# debug.net
KiCad netlist of a schematic drawn in Altium Designer
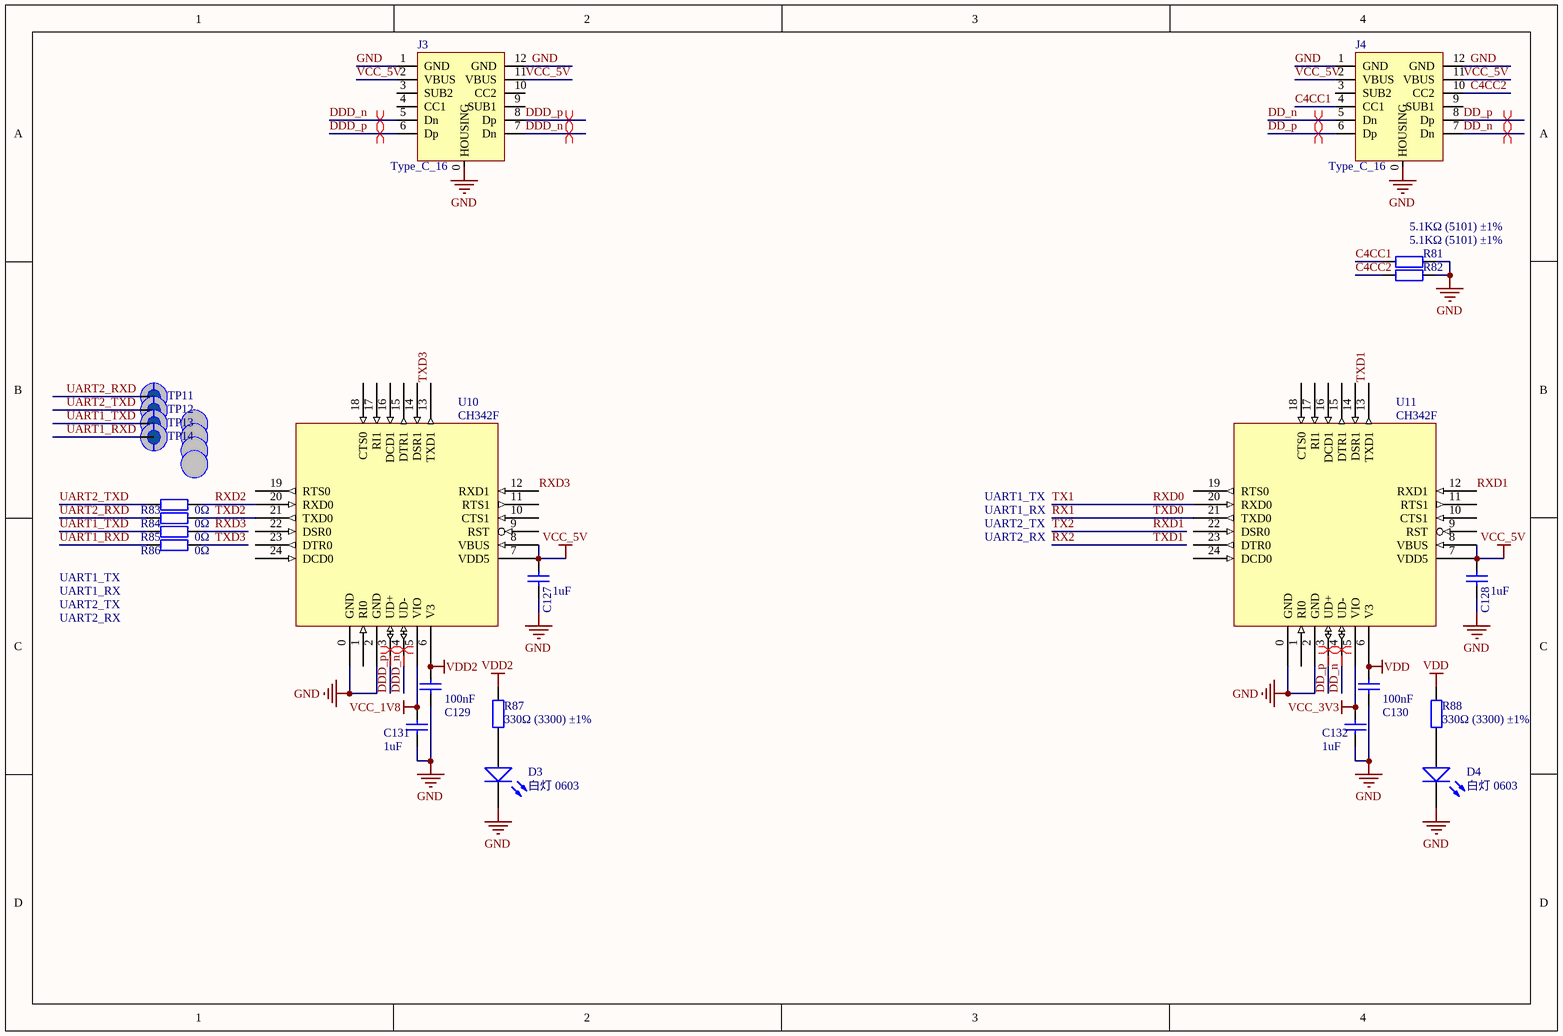
[diagram p0: debug.SchDoc]

(export (version "E")
  (design (tool "Eeschema 10.0.6"))
  (components
    (comp (ref "C127")
      (value "1uF")
      (footprint "0805_C")
      (description "贴片电容")
      (libsource (lib "嘉立创标准库") (part "0603 1uF (105) 10% 50V"))
    )
    (comp (ref "C128")
      (value "1uF")
      (footprint "0805_C")
      (description "贴片电容")
      (libsource (lib "嘉立创标准库") (part "0603 1uF (105) 10% 50V"))
    )
    (comp (ref "C129")
      (value "100nF")
      (footprint "0805_C")
      (description "贴片电容")
      (libsource (lib "嘉立创标准库") (part "0402 100nF (104) 10% 16V"))
    )
    (comp (ref "C130")
      (value "100nF")
      (footprint "0805_C")
      (description "贴片电容")
      (libsource (lib "嘉立创标准库") (part "0402 100nF (104) 10% 16V"))
    )
    (comp (ref "C131")
      (value "1uF")
      (footprint "0805_C")
      (description "贴片电容")
      (libsource (lib "嘉立创标准库") (part "0603 1uF (105) 10% 50V"))
    )
    (comp (ref "C132")
      (value "1uF")
      (footprint "0805_C")
      (description "贴片电容")
      (libsource (lib "嘉立创标准库") (part "0603 1uF (105) 10% 50V"))
    )
    (comp (ref "D3")
      (value "白灯 0603")
      (footprint "0805_LED_S1")
      (description "发光二极管")
      (libsource (lib "嘉立创标准库") (part "0603 白灯"))
    )
    (comp (ref "D4")
      (value "白灯 0603")
      (footprint "0805_LED_S1")
      (description "发光二极管")
      (libsource (lib "嘉立创标准库") (part "0603 白灯"))
    )
    (comp (ref "J3")
      (value "Type_C_16")
      (footprint "USB type C  16pin")
      (description "USB type C 16pin")
      (libsource (lib "yy_tech") (part "Type_C_16"))
    )
    (comp (ref "J4")
      (value "Type_C_16")
      (footprint "USB type C  16pin")
      (description "USB type C 16pin")
      (libsource (lib "yy_tech") (part "Type_C_16"))
    )
    (comp (ref "R81")
      (value "5.1KΩ (5101) ±1%")
      (footprint "0402_R")
      (description "贴片电阻")
      (libsource (lib "嘉立创标准库") (part "0402 5.1KΩ (5101) 1%"))
    )
    (comp (ref "R82")
      (value "5.1KΩ (5101) ±1%")
      (footprint "0402_R")
      (description "贴片电阻")
      (libsource (lib "嘉立创标准库") (part "0402 5.1KΩ (5101) 1%"))
    )
    (comp (ref "R83")
      (value "0Ω")
      (footprint "0805_R")
      (description "贴片电阻")
      (libsource (lib "Miscellaneous Devices LC") (part "0805 0Ω (0R0) 1%"))
    )
    (comp (ref "R84")
      (value "0Ω")
      (footprint "0805_R")
      (description "贴片电阻")
      (libsource (lib "Miscellaneous Devices LC") (part "0805 0Ω (0R0) 1%"))
    )
    (comp (ref "R85")
      (value "0Ω")
      (footprint "0805_R")
      (description "贴片电阻")
      (libsource (lib "Miscellaneous Devices LC") (part "0805 0Ω (0R0) 1%"))
    )
    (comp (ref "R86")
      (value "0Ω")
      (footprint "0805_R")
      (description "贴片电阻")
      (libsource (lib "Miscellaneous Devices LC") (part "0805 0Ω (0R0) 1%"))
    )
    (comp (ref "R87")
      (value "330Ω (3300) ±1%")
      (footprint "0805_R")
      (description "贴片电阻")
      (libsource (lib "Miscellaneous Devices LC") (part "0402 330Ω (3300) 1%"))
    )
    (comp (ref "R88")
      (value "330Ω (3300) ±1%")
      (footprint "0805_R")
      (description "贴片电阻")
      (libsource (lib "Miscellaneous Devices LC") (part "0402 330Ω (3300) 1%"))
    )
    (comp (ref "TP11")
      (value "test-point")
      (footprint "POINT")
      (description "测试点")
      (libsource (lib "五向开关") (part "test-point"))
    )
    (comp (ref "TP12")
      (value "test-point")
      (footprint "POINT")
      (description "测试点")
      (libsource (lib "五向开关") (part "test-point"))
    )
    (comp (ref "TP13")
      (value "test-point")
      (footprint "POINT")
      (description "测试点")
      (libsource (lib "五向开关") (part "test-point"))
    )
    (comp (ref "TP14")
      (value "test-point")
      (footprint "POINT")
      (description "测试点")
      (libsource (lib "五向开关") (part "test-point"))
    )
    (comp (ref "U10")
      (value "CH342F")
      (footprint "QFN24_4X4")
      (description "USB to dual enhanced TTL Serial / 2*UART")
      (libsource (lib "CHXXX") (part "CH342F"))
    )
    (comp (ref "U11")
      (value "CH342F")
      (footprint "QFN24_4X4")
      (description "USB to dual enhanced TTL Serial / 2*UART")
      (libsource (lib "CHXXX") (part "CH342F"))
    )
  )
  (nets
    (net (code "1") (name "/C4CC1") (class "Default")
      (node (ref "J4") (pin "4") (pinfunction "CC1_4") (pintype "passive"))
      (node (ref "R81") (pin "2") (pinfunction "2_2") (pintype "passive"))
    )
    (net (code "2") (name "/C4CC2") (class "Default")
      (node (ref "J4") (pin "10") (pinfunction "CC2_10") (pintype "passive"))
      (node (ref "R82") (pin "2") (pinfunction "2_2") (pintype "passive"))
    )
    (net (code "3") (name "/DDD_n") (class "Default")
      (node (ref "J3") (pin "5") (pinfunction "Dn_5") (pintype "passive"))
      (node (ref "J3") (pin "7") (pinfunction "Dn_7") (pintype "passive"))
      (node (ref "U10") (pin "4") (pinfunction "UD-_4") (pintype "bidirectional"))
    )
    (net (code "4") (name "/DDD_p") (class "Default")
      (node (ref "J3") (pin "6") (pinfunction "Dp_6") (pintype "passive"))
      (node (ref "J3") (pin "8") (pinfunction "Dp_8") (pintype "passive"))
      (node (ref "U10") (pin "3") (pinfunction "UD+_3") (pintype "bidirectional"))
    )
    (net (code "5") (name "/DD_n") (class "Default")
      (node (ref "J4") (pin "5") (pinfunction "Dn_5") (pintype "passive"))
      (node (ref "J4") (pin "7") (pinfunction "Dn_7") (pintype "passive"))
      (node (ref "U11") (pin "4") (pinfunction "UD-_4") (pintype "bidirectional"))
    )
    (net (code "6") (name "/DD_p") (class "Default")
      (node (ref "J4") (pin "6") (pinfunction "Dp_6") (pintype "passive"))
      (node (ref "J4") (pin "8") (pinfunction "Dp_8") (pintype "passive"))
      (node (ref "U11") (pin "3") (pinfunction "UD+_3") (pintype "bidirectional"))
    )
    (net (code "7") (name "/RX1") (class "Default")
      (node (ref "U11") (pin "21") (pinfunction "TXD0_21") (pintype "output"))
    )
    (net (code "8") (name "/RX2") (class "Default")
      (node (ref "U11") (pin "13") (pinfunction "TXD1_13") (pintype "output"))
    )
    (net (code "9") (name "/RXD0") (class "Default")
      (node (ref "U11") (pin "20") (pinfunction "RXD0_20") (pintype "input"))
    )
    (net (code "10") (name "/RXD1") (class "Default")
      (node (ref "U11") (pin "12") (pinfunction "RXD1_12") (pintype "input"))
    )
    (net (code "11") (name "/RXD2") (class "Default")
      (node (ref "R83") (pin "2") (pinfunction "2_2") (pintype "passive"))
      (node (ref "U10") (pin "20") (pinfunction "RXD0_20") (pintype "input"))
    )
    (net (code "12") (name "/RXD3") (class "Default")
      (node (ref "R85") (pin "2") (pinfunction "2_2") (pintype "passive"))
      (node (ref "U10") (pin "12") (pinfunction "RXD1_12") (pintype "input"))
    )
    (net (code "13") (name "/TXD2") (class "Default")
      (node (ref "R84") (pin "2") (pinfunction "2_2") (pintype "passive"))
      (node (ref "U10") (pin "21") (pinfunction "TXD0_21") (pintype "output"))
    )
    (net (code "14") (name "/TXD3") (class "Default")
      (node (ref "R86") (pin "2") (pinfunction "2_2") (pintype "passive"))
      (node (ref "U10") (pin "13") (pinfunction "TXD1_13") (pintype "output"))
    )
    (net (code "15") (name "/UART1_RXD") (class "Default")
      (node (ref "R86") (pin "1") (pinfunction "1_1") (pintype "passive"))
      (node (ref "TP14") (pin "1") (pinfunction "point_1") (pintype "passive"))
    )
    (net (code "16") (name "/UART1_TXD") (class "Default")
      (node (ref "R85") (pin "1") (pinfunction "1_1") (pintype "passive"))
      (node (ref "TP13") (pin "1") (pinfunction "point_1") (pintype "passive"))
    )
    (net (code "17") (name "/UART2_RXD") (class "Default")
      (node (ref "R84") (pin "1") (pinfunction "1_1") (pintype "passive"))
      (node (ref "TP11") (pin "1") (pinfunction "point_1") (pintype "passive"))
    )
    (net (code "18") (name "/UART2_TXD") (class "Default")
      (node (ref "R83") (pin "1") (pinfunction "1_1") (pintype "passive"))
      (node (ref "TP12") (pin "1") (pinfunction "point_1") (pintype "passive"))
    )
    (net (code "19") (name "GND") (class "Default")
      (node (ref "C127") (pin "1") (pinfunction "1_1") (pintype "passive"))
      (node (ref "C128") (pin "1") (pinfunction "1_1") (pintype "passive"))
      (node (ref "C129") (pin "1") (pinfunction "1_1") (pintype "passive"))
      (node (ref "C130") (pin "1") (pinfunction "1_1") (pintype "passive"))
      (node (ref "C131") (pin "1") (pinfunction "1_1") (pintype "passive"))
      (node (ref "C132") (pin "1") (pinfunction "1_1") (pintype "passive"))
      (node (ref "D3") (pin "K") (pinfunction "K_K") (pintype "passive"))
      (node (ref "D4") (pin "K") (pinfunction "K_K") (pintype "passive"))
      (node (ref "J3") (pin "0") (pinfunction "HOUSING_0") (pintype "passive"))
      (node (ref "J3") (pin "1") (pinfunction "GND_1") (pintype "passive"))
      (node (ref "J3") (pin "12") (pinfunction "GND_12") (pintype "passive"))
      (node (ref "J4") (pin "0") (pinfunction "HOUSING_0") (pintype "passive"))
      (node (ref "J4") (pin "1") (pinfunction "GND_1") (pintype "passive"))
      (node (ref "J4") (pin "12") (pinfunction "GND_12") (pintype "passive"))
      (node (ref "R81") (pin "1") (pinfunction "1_1") (pintype "passive"))
      (node (ref "R82") (pin "1") (pinfunction "1_1") (pintype "passive"))
      (node (ref "U10") (pin "0") (pinfunction "GND_0") (pintype "power_in"))
      (node (ref "U10") (pin "2") (pinfunction "GND_2") (pintype "power_in"))
      (node (ref "U11") (pin "0") (pinfunction "GND_0") (pintype "power_in"))
      (node (ref "U11") (pin "2") (pinfunction "GND_2") (pintype "power_in"))
    )
    (net (code "20") (name "Net-(D3-PadA)") (class "Default")
      (node (ref "D3") (pin "A") (pinfunction "A_A") (pintype "passive"))
      (node (ref "R87") (pin "1") (pinfunction "1_1") (pintype "passive"))
    )
    (net (code "21") (name "Net-(D4-PadA)") (class "Default")
      (node (ref "D4") (pin "A") (pinfunction "A_A") (pintype "passive"))
      (node (ref "R88") (pin "1") (pinfunction "1_1") (pintype "passive"))
    )
    (net (code "22") (name "VCC_1V8") (class "Default")
      (node (ref "C131") (pin "2") (pinfunction "2_2") (pintype "passive"))
      (node (ref "U10") (pin "5") (pinfunction "VIO_5") (pintype "power_in"))
    )
    (net (code "23") (name "VCC_3V3") (class "Default")
      (node (ref "C132") (pin "2") (pinfunction "2_2") (pintype "passive"))
      (node (ref "U11") (pin "5") (pinfunction "VIO_5") (pintype "power_in"))
    )
    (net (code "24") (name "VCC_5V") (class "Default")
      (node (ref "C127") (pin "2") (pinfunction "2_2") (pintype "passive"))
      (node (ref "C128") (pin "2") (pinfunction "2_2") (pintype "passive"))
      (node (ref "J3") (pin "11") (pinfunction "VBUS_11") (pintype "passive"))
      (node (ref "J3") (pin "2") (pinfunction "VBUS_2") (pintype "passive"))
      (node (ref "J4") (pin "11") (pinfunction "VBUS_11") (pintype "passive"))
      (node (ref "J4") (pin "2") (pinfunction "VBUS_2") (pintype "passive"))
      (node (ref "U10") (pin "7") (pinfunction "VDD5_7") (pintype "power_in"))
      (node (ref "U10") (pin "8") (pinfunction "VBUS_8") (pintype "input"))
      (node (ref "U11") (pin "7") (pinfunction "VDD5_7") (pintype "power_in"))
      (node (ref "U11") (pin "8") (pinfunction "VBUS_8") (pintype "input"))
    )
    (net (code "25") (name "VDD") (class "Default")
      (node (ref "C130") (pin "2") (pinfunction "2_2") (pintype "passive"))
      (node (ref "R88") (pin "2") (pinfunction "2_2") (pintype "passive"))
      (node (ref "U11") (pin "6") (pinfunction "V3_6") (pintype "power_in"))
    )
    (net (code "26") (name "VDD2") (class "Default")
      (node (ref "C129") (pin "2") (pinfunction "2_2") (pintype "passive"))
      (node (ref "R87") (pin "2") (pinfunction "2_2") (pintype "passive"))
      (node (ref "U10") (pin "6") (pinfunction "V3_6") (pintype "power_in"))
    )
    (net (code "27") (name "unconnected-(J3-CC1-Pad4)") (class "Default")
      (node (ref "J3") (pin "4") (pinfunction "CC1_4") (pintype "passive"))
    )
    (net (code "28") (name "unconnected-(J3-CC2-Pad10)") (class "Default")
      (node (ref "J3") (pin "10") (pinfunction "CC2_10") (pintype "passive"))
    )
    (net (code "29") (name "unconnected-(J3-SUB1-Pad9)") (class "Default")
      (node (ref "J3") (pin "9") (pinfunction "SUB1_9") (pintype "passive"))
    )
    (net (code "30") (name "unconnected-(J3-SUB2-Pad3)") (class "Default")
      (node (ref "J3") (pin "3") (pinfunction "SUB2_3") (pintype "passive"))
    )
    (net (code "31") (name "unconnected-(J4-SUB1-Pad9)") (class "Default")
      (node (ref "J4") (pin "9") (pinfunction "SUB1_9") (pintype "passive"))
    )
    (net (code "32") (name "unconnected-(J4-SUB2-Pad3)") (class "Default")
      (node (ref "J4") (pin "3") (pinfunction "SUB2_3") (pintype "passive"))
    )
    (net (code "33") (name "unconnected-(U10-CTS0-Pad18)") (class "Default")
      (node (ref "U10") (pin "18") (pinfunction "CTS0_18") (pintype "input"))
    )
    (net (code "34") (name "unconnected-(U10-CTS1-Pad10)") (class "Default")
      (node (ref "U10") (pin "10") (pinfunction "CTS1_10") (pintype "input"))
    )
    (net (code "35") (name "unconnected-(U10-DCD0-Pad24)") (class "Default")
      (node (ref "U10") (pin "24") (pinfunction "DCD0_24") (pintype "input"))
    )
    (net (code "36") (name "unconnected-(U10-DCD1-Pad16)") (class "Default")
      (node (ref "U10") (pin "16") (pinfunction "DCD1_16") (pintype "input"))
    )
    (net (code "37") (name "unconnected-(U10-DSR0-Pad22)") (class "Default")
      (node (ref "U10") (pin "22") (pinfunction "DSR0_22") (pintype "input"))
    )
    (net (code "38") (name "unconnected-(U10-DSR1-Pad14)") (class "Default")
      (node (ref "U10") (pin "14") (pinfunction "DSR1_14") (pintype "input"))
    )
    (net (code "39") (name "unconnected-(U10-DTR0-Pad23)") (class "Default")
      (node (ref "U10") (pin "23") (pinfunction "DTR0_23") (pintype "output"))
    )
    (net (code "40") (name "unconnected-(U10-DTR1-Pad15)") (class "Default")
      (node (ref "U10") (pin "15") (pinfunction "DTR1_15") (pintype "output"))
    )
    (net (code "41") (name "unconnected-(U10-RI0-Pad1)") (class "Default")
      (node (ref "U10") (pin "1") (pinfunction "RI0_1") (pintype "input"))
    )
    (net (code "42") (name "unconnected-(U10-RI1-Pad17)") (class "Default")
      (node (ref "U10") (pin "17") (pinfunction "RI1_17") (pintype "input"))
    )
    (net (code "43") (name "unconnected-(U10-RST-Pad9)") (class "Default")
      (node (ref "U10") (pin "9") (pinfunction "RST_9") (pintype "input"))
    )
    (net (code "44") (name "unconnected-(U10-RTS0-Pad19)") (class "Default")
      (node (ref "U10") (pin "19") (pinfunction "RTS0_19") (pintype "output"))
    )
    (net (code "45") (name "unconnected-(U10-RTS1-Pad11)") (class "Default")
      (node (ref "U10") (pin "11") (pinfunction "RTS1_11") (pintype "output"))
    )
    (net (code "46") (name "unconnected-(U11-CTS0-Pad18)") (class "Default")
      (node (ref "U11") (pin "18") (pinfunction "CTS0_18") (pintype "input"))
    )
    (net (code "47") (name "unconnected-(U11-CTS1-Pad10)") (class "Default")
      (node (ref "U11") (pin "10") (pinfunction "CTS1_10") (pintype "input"))
    )
    (net (code "48") (name "unconnected-(U11-DCD0-Pad24)") (class "Default")
      (node (ref "U11") (pin "24") (pinfunction "DCD0_24") (pintype "input"))
    )
    (net (code "49") (name "unconnected-(U11-DCD1-Pad16)") (class "Default")
      (node (ref "U11") (pin "16") (pinfunction "DCD1_16") (pintype "input"))
    )
    (net (code "50") (name "unconnected-(U11-DSR0-Pad22)") (class "Default")
      (node (ref "U11") (pin "22") (pinfunction "DSR0_22") (pintype "input"))
    )
    (net (code "51") (name "unconnected-(U11-DSR1-Pad14)") (class "Default")
      (node (ref "U11") (pin "14") (pinfunction "DSR1_14") (pintype "input"))
    )
    (net (code "52") (name "unconnected-(U11-DTR0-Pad23)") (class "Default")
      (node (ref "U11") (pin "23") (pinfunction "DTR0_23") (pintype "output"))
    )
    (net (code "53") (name "unconnected-(U11-DTR1-Pad15)") (class "Default")
      (node (ref "U11") (pin "15") (pinfunction "DTR1_15") (pintype "output"))
    )
    (net (code "54") (name "unconnected-(U11-RI0-Pad1)") (class "Default")
      (node (ref "U11") (pin "1") (pinfunction "RI0_1") (pintype "input"))
    )
    (net (code "55") (name "unconnected-(U11-RI1-Pad17)") (class "Default")
      (node (ref "U11") (pin "17") (pinfunction "RI1_17") (pintype "input"))
    )
    (net (code "56") (name "unconnected-(U11-RST-Pad9)") (class "Default")
      (node (ref "U11") (pin "9") (pinfunction "RST_9") (pintype "input"))
    )
    (net (code "57") (name "unconnected-(U11-RTS0-Pad19)") (class "Default")
      (node (ref "U11") (pin "19") (pinfunction "RTS0_19") (pintype "output"))
    )
    (net (code "58") (name "unconnected-(U11-RTS1-Pad11)") (class "Default")
      (node (ref "U11") (pin "11") (pinfunction "RTS1_11") (pintype "output"))
    )
  )
)
